# AUDIO2.net
KiCad netlist of a schematic drawn in Altium Designer
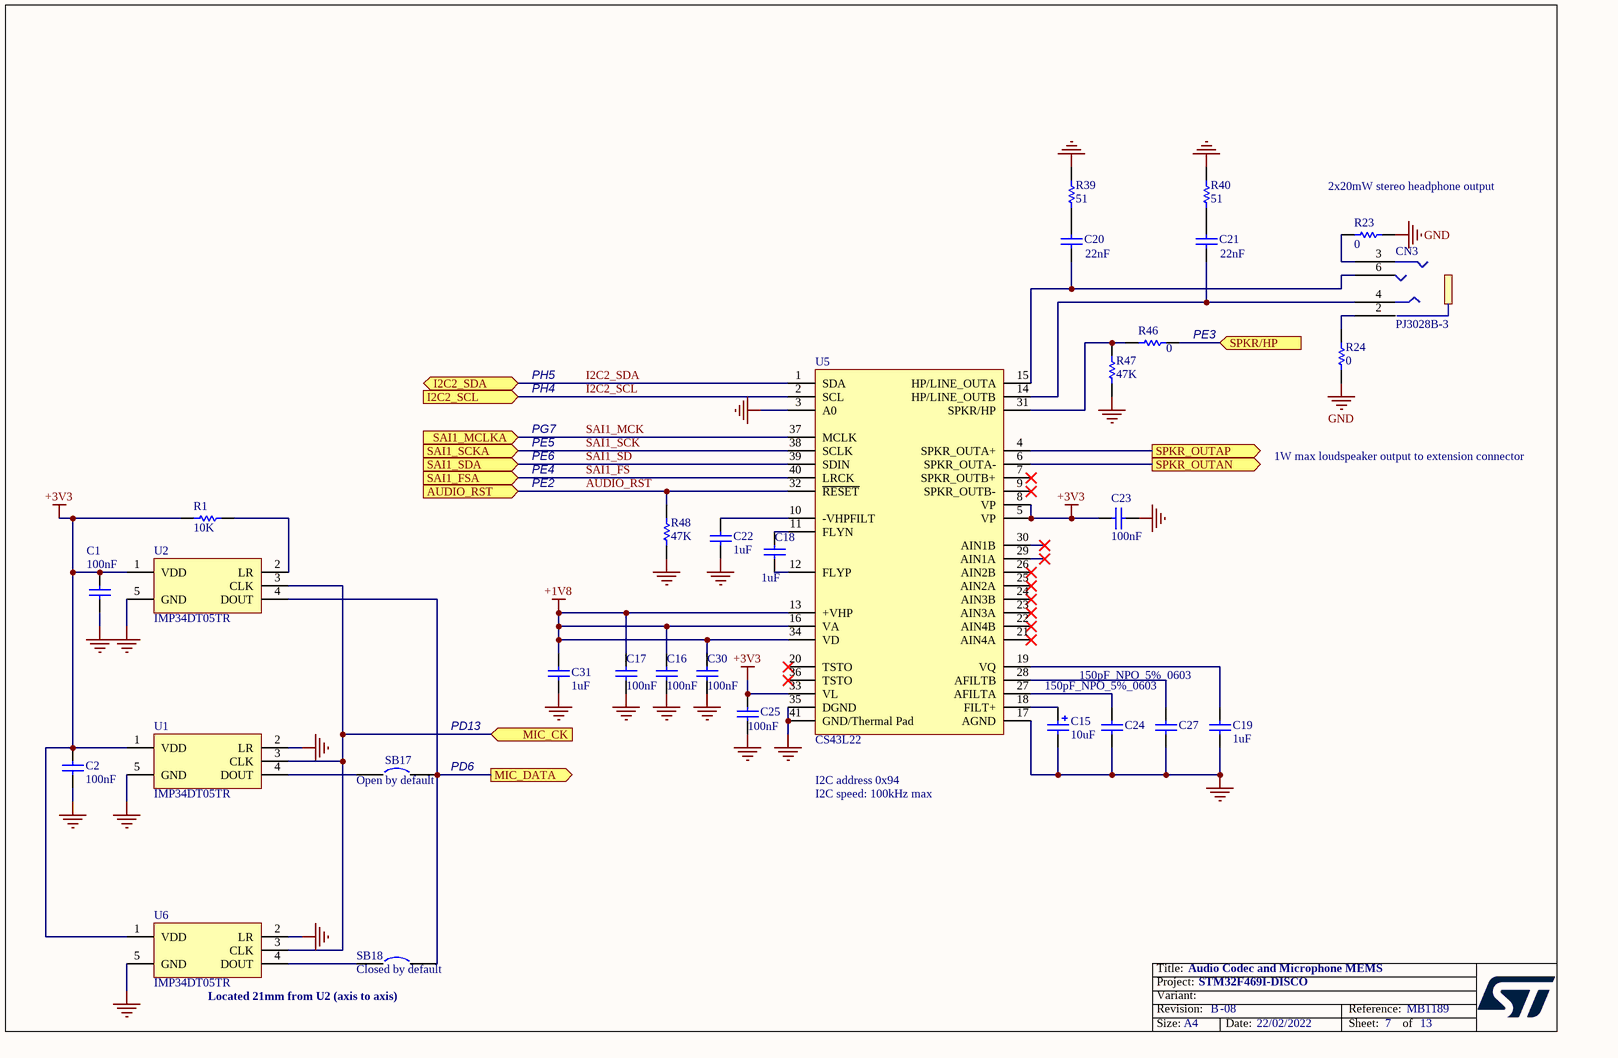
[diagram p0: AUDIO2.SchDoc]

(export (version "E")
  (design (tool "Eeschema 10.0.6"))
  (components
    (comp (ref "C1")
      (value "100nF")
      (footprint "0402C")
      (description "Capacitor")
      (fields (field (name "PUBLISHER") "Altium Limited"))
      (libsource (lib "Miscellaneous Devices") (part "Cap"))
    )
    (comp (ref "C2")
      (value "100nF")
      (footprint "0402C")
      (description "Capacitor")
      (fields (field (name "PUBLISHER") "Altium Limited"))
      (libsource (lib "Miscellaneous Devices") (part "Cap"))
    )
    (comp (ref "C15")
      (value "10uF")
      (footprint "TAN-A")
      (description "Polarized Capacitor (Radial)")
      (fields (field (name "PUBLISHER") "Altium Limited"))
      (libsource (lib "Miscellaneous Devices") (part "Cap Pol1"))
    )
    (comp (ref "C16")
      (value "100nF")
      (footprint "0402C")
      (description "Capacitor")
      (fields (field (name "PUBLISHER") "Altium Limited"))
      (libsource (lib "Miscellaneous Devices") (part "CAP"))
    )
    (comp (ref "C17")
      (value "100nF")
      (footprint "0402C")
      (description "Capacitor")
      (fields (field (name "PUBLISHER") "Altium Limited"))
      (libsource (lib "Miscellaneous Devices") (part "CAP"))
    )
    (comp (ref "C18")
      (value "1uF")
      (footprint "0603C")
      (description "Capacitor")
      (fields (field (name "PUBLISHER") "Altium Limited"))
      (libsource (lib "Miscellaneous Devices") (part "CAP"))
    )
    (comp (ref "C19")
      (value "1uF")
      (footprint "0603C")
      (description "Capacitor")
      (fields (field (name "PUBLISHER") "Altium Limited"))
      (libsource (lib "Miscellaneous Devices") (part "CAP"))
    )
    (comp (ref "C20")
      (value "22nF")
      (footprint "0603C")
      (description "Capacitor,22nF,50V,X7R,10%,0603,YAGEO")
      (libsource (lib "MCD_TOOLS") (part "Cap_22nF_X7R_10%_0603"))
    )
    (comp (ref "C21")
      (value "22nF")
      (footprint "0603C")
      (description "Capacitor,22nF,50V,X7R,10%,0603,YAGEO")
      (libsource (lib "MCD_TOOLS") (part "Cap_22nF_X7R_10%_0603"))
    )
    (comp (ref "C22")
      (value "1uF")
      (footprint "0603C")
      (description "Capacitor")
      (fields (field (name "PUBLISHER") "Altium Limited"))
      (libsource (lib "Miscellaneous Devices") (part "CAP"))
    )
    (comp (ref "C23")
      (value "100nF")
      (footprint "0402C")
      (description "Capacitor")
      (fields (field (name "PUBLISHER") "Altium Limited"))
      (libsource (lib "Miscellaneous Devices") (part "CAP"))
    )
    (comp (ref "C24")
      (value "150pF_NPO_5%_0603")
      (footprint "0603C")
      (description "Capacitor,150pF,50V,NPO,5%,0603,YAGEO")
      (libsource (lib "MCD_TOOLS") (part "Cap_150pF_NPO_5%_0603"))
    )
    (comp (ref "C25")
      (value "100nF")
      (footprint "0402C")
      (description "Capacitor")
      (fields (field (name "PUBLISHER") "Altium Limited"))
      (libsource (lib "Miscellaneous Devices") (part "CAP"))
    )
    (comp (ref "C27")
      (value "150pF_NPO_5%_0603")
      (footprint "0603C")
      (description "Capacitor,150pF,50V,NPO,5%,0603,YAGEO")
      (libsource (lib "MCD_TOOLS") (part "Cap_150pF_NPO_5%_0603"))
    )
    (comp (ref "C30")
      (value "100nF")
      (footprint "0402C")
      (description "Capacitor")
      (fields (field (name "PUBLISHER") "Altium Limited"))
      (libsource (lib "Miscellaneous Devices") (part "CAP"))
    )
    (comp (ref "C31")
      (value "1uF")
      (footprint "0603C")
      (description "Capacitor")
      (fields (field (name "PUBLISHER") "Altium Limited"))
      (libsource (lib "Miscellaneous Devices") (part "CAP"))
    )
    (comp (ref "CN3") (value "PJ3028B-3") (footprint "PJ3028B") (libsource (lib "MB786") (part "PJ3028B-3")))
    (comp (ref "R1")
      (value "10K")
      (footprint "0603R")
      (description "Resistor")
      (libsource (lib "MCD_TOOLS") (part "Res_0_5%_0402"))
    )
    (comp (ref "R23")
      (value "0")
      (footprint "0603R")
      (description "Resistor")
      (fields (field (name "PUBLISHER") "Altium Limited"))
      (libsource (lib "") (part "Res1_1"))
    )
    (comp (ref "R24")
      (value "0")
      (footprint "0603R")
      (description "Resistor")
      (fields (field (name "PUBLISHER") "Altium Limited"))
      (libsource (lib "") (part "Res1_1"))
    )
    (comp (ref "R39")
      (value "51")
      (footprint "0402R")
      (description "Resistor")
      (libsource (lib "MCD_TOOLS") (part "Res_51_1%_0402"))
    )
    (comp (ref "R40")
      (value "51")
      (footprint "0402R")
      (description "Resistor")
      (libsource (lib "MCD_TOOLS") (part "Res_51_1%_0402"))
    )
    (comp (ref "R46")
      (value "0")
      (footprint "0603R")
      (description "Resistor")
      (fields (field (name "PUBLISHER") "Altium Limited"))
      (libsource (lib "Miscellaneous Devices") (part "Res1"))
    )
    (comp (ref "R47")
      (value "47K")
      (footprint "0603R")
      (description "Resistor")
      (fields (field (name "PUBLISHER") "Altium Limited"))
      (libsource (lib "Miscellaneous Devices") (part "Res1"))
    )
    (comp (ref "R48")
      (value "47K")
      (footprint "0603R")
      (description "Resistor")
      (fields (field (name "PUBLISHER") "Altium Limited"))
      (libsource (lib "Miscellaneous Devices") (part "Res1"))
    )
    (comp (ref "SB17")
      (value "Open by default")
      (footprint "SB_0603")
      (description "Circuit Breaker")
      (fields (field (name "PUBLISHER") "Altium Limited"))
      (libsource (lib "Miscellaneous Devices") (part "Circuit Breaker"))
    )
    (comp (ref "SB18")
      (value "Closed by default")
      (footprint "SB_0603")
      (description "Circuit Breaker")
      (fields (field (name "PUBLISHER") "Altium Limited"))
      (libsource (lib "Miscellaneous Devices") (part "Circuit Breaker"))
    )
    (comp (ref "U1")
      (value "IMP34DT05TR")
      (footprint "MP34DT01TR")
      (description "MEMS audio sensor")
      (libsource (lib "Almos") (part "MP34DT01TR"))
    )
    (comp (ref "U2")
      (value "IMP34DT05TR")
      (footprint "MP34DT01TR")
      (description "MEMS audio sensor")
      (libsource (lib "Almos") (part "MP34DT01TR"))
    )
    (comp (ref "U5")
      (value "CS43L22")
      (footprint "QFN40_0R5_6X6")
      (description "Low Power, Stereo DAC w/Headphone & Speaker Amps")
      (libsource (lib "MCD_TOOLS") (part "CS43L22"))
    )
    (comp (ref "U6")
      (value "IMP34DT05TR")
      (footprint "MP34DT01TR")
      (description "MEMS audio sensor")
      (libsource (lib "Almos") (part "MP34DT01TR"))
    )
  )
  (nets
    (net (code "1") (name "+1V8") (class "Default")
      (node (ref "C16") (pin "1") (pinfunction "1_1") (pintype "passive"))
      (node (ref "C17") (pin "1") (pinfunction "1_1") (pintype "passive"))
      (node (ref "C30") (pin "1") (pinfunction "1_1") (pintype "passive"))
      (node (ref "C31") (pin "1") (pinfunction "1_1") (pintype "passive"))
      (node (ref "U5") (pin "13") (pinfunction "+VHP_13") (pintype "passive"))
      (node (ref "U5") (pin "16") (pinfunction "VA_16") (pintype "passive"))
      (node (ref "U5") (pin "34") (pinfunction "VD_34") (pintype "passive"))
    )
    (net (code "2") (name "+3V3") (class "Default")
      (node (ref "C1") (pin "2") (pinfunction "2_2") (pintype "passive"))
      (node (ref "C2") (pin "2") (pinfunction "2_2") (pintype "passive"))
      (node (ref "C23") (pin "2") (pinfunction "2_2") (pintype "passive"))
      (node (ref "C25") (pin "1") (pinfunction "1_1") (pintype "passive"))
      (node (ref "R1") (pin "2") (pinfunction "2_2") (pintype "passive"))
      (node (ref "U1") (pin "1") (pinfunction "VDD_1") (pintype "passive"))
      (node (ref "U2") (pin "1") (pinfunction "VDD_1") (pintype "passive"))
      (node (ref "U5") (pin "33") (pinfunction "VL_33") (pintype "passive"))
      (node (ref "U5") (pin "5") (pinfunction "VP_5") (pintype "passive"))
      (node (ref "U5") (pin "8") (pinfunction "VP_8") (pintype "passive"))
      (node (ref "U6") (pin "1") (pinfunction "VDD_1") (pintype "passive"))
    )
    (net (code "3") (name "/AUDIO_RST") (class "Default")
      (node (ref "R48") (pin "2") (pinfunction "2_2") (pintype "passive"))
      (node (ref "U5") (pin "32") (pinfunction "~{RESET}_32") (pintype "passive"))
    )
    (net (code "4") (name "/I2C2_SCL") (class "Default")
      (node (ref "U5") (pin "2") (pinfunction "SCL_2") (pintype "passive"))
    )
    (net (code "5") (name "/I2C2_SDA") (class "Default")
      (node (ref "U5") (pin "1") (pinfunction "SDA_1") (pintype "passive"))
    )
    (net (code "6") (name "/MIC_CK") (class "Default")
      (node (ref "U1") (pin "3") (pinfunction "CLK_3") (pintype "passive"))
      (node (ref "U2") (pin "3") (pinfunction "CLK_3") (pintype "passive"))
      (node (ref "U6") (pin "3") (pinfunction "CLK_3") (pintype "passive"))
    )
    (net (code "7") (name "/MIC_DATA") (class "Default")
      (node (ref "SB17") (pin "2") (pinfunction "2_2") (pintype "passive"))
      (node (ref "SB18") (pin "2") (pinfunction "2_2") (pintype "passive"))
      (node (ref "U2") (pin "4") (pinfunction "DOUT_4") (pintype "passive"))
    )
    (net (code "8") (name "/SAI1_FS") (class "Default")
      (node (ref "U5") (pin "40") (pinfunction "LRCK_40") (pintype "passive"))
    )
    (net (code "9") (name "/SAI1_MCK") (class "Default")
      (node (ref "U5") (pin "37") (pinfunction "MCLK_37") (pintype "passive"))
    )
    (net (code "10") (name "/SAI1_SCK") (class "Default")
      (node (ref "U5") (pin "38") (pinfunction "SCLK_38") (pintype "passive"))
    )
    (net (code "11") (name "/SAI1_SD") (class "Default")
      (node (ref "U5") (pin "39") (pinfunction "SDIN_39") (pintype "passive"))
    )
    (net (code "12") (name "/SPKR_OUTAN") (class "Default")
      (node (ref "U5") (pin "6") (pinfunction "SPKR_OUTA-_6") (pintype "passive"))
    )
    (net (code "13") (name "/SPKR_OUTAP") (class "Default")
      (node (ref "U5") (pin "4") (pinfunction "SPKR_OUTA+_4") (pintype "passive"))
    )
    (net (code "14") (name "/SPKR{slash}HP") (class "Default")
      (node (ref "R46") (pin "2") (pinfunction "2_2") (pintype "passive"))
    )
    (net (code "15") (name "GND") (class "Default")
      (node (ref "C1") (pin "1") (pinfunction "1_1") (pintype "passive"))
      (node (ref "C15") (pin "2") (pinfunction "2_2") (pintype "passive"))
      (node (ref "C16") (pin "2") (pinfunction "2_2") (pintype "passive"))
      (node (ref "C17") (pin "2") (pinfunction "2_2") (pintype "passive"))
      (node (ref "C19") (pin "1") (pinfunction "1_1") (pintype "passive"))
      (node (ref "C2") (pin "1") (pinfunction "1_1") (pintype "passive"))
      (node (ref "C22") (pin "1") (pinfunction "1_1") (pintype "passive"))
      (node (ref "C23") (pin "1") (pinfunction "1_1") (pintype "passive"))
      (node (ref "C24") (pin "1") (pinfunction "1_1") (pintype "passive"))
      (node (ref "C25") (pin "2") (pinfunction "2_2") (pintype "passive"))
      (node (ref "C27") (pin "1") (pinfunction "1_1") (pintype "passive"))
      (node (ref "C30") (pin "2") (pinfunction "2_2") (pintype "passive"))
      (node (ref "C31") (pin "2") (pinfunction "2_2") (pintype "passive"))
      (node (ref "R23") (pin "2") (pinfunction "2_2") (pintype "passive"))
      (node (ref "R24") (pin "2") (pinfunction "2_2") (pintype "passive"))
      (node (ref "R39") (pin "2") (pinfunction "2_2") (pintype "passive"))
      (node (ref "R40") (pin "2") (pinfunction "2_2") (pintype "passive"))
      (node (ref "R47") (pin "2") (pinfunction "2_2") (pintype "passive"))
      (node (ref "R48") (pin "1") (pinfunction "1_1") (pintype "passive"))
      (node (ref "U1") (pin "2") (pinfunction "LR_2") (pintype "passive"))
      (node (ref "U1") (pin "5") (pinfunction "GND_5") (pintype "passive"))
      (node (ref "U2") (pin "5") (pinfunction "GND_5") (pintype "passive"))
      (node (ref "U5") (pin "17") (pinfunction "AGND_17") (pintype "passive"))
      (node (ref "U5") (pin "3") (pinfunction "A0_3") (pintype "passive"))
      (node (ref "U5") (pin "35") (pinfunction "DGND_35") (pintype "passive"))
      (node (ref "U5") (pin "41") (pinfunction "GND/Thermal_Pad_41") (pintype "passive"))
      (node (ref "U6") (pin "2") (pinfunction "LR_2") (pintype "passive"))
      (node (ref "U6") (pin "5") (pinfunction "GND_5") (pintype "passive"))
    )
    (net (code "16") (name "Net-(C20-Pad2)") (class "Default")
      (node (ref "C20") (pin "2") (pinfunction "2_2") (pintype "passive"))
      (node (ref "R39") (pin "1") (pinfunction "1_1") (pintype "passive"))
    )
    (net (code "17") (name "Net-(C21-Pad2)") (class "Default")
      (node (ref "C21") (pin "2") (pinfunction "2_2") (pintype "passive"))
      (node (ref "R40") (pin "1") (pinfunction "1_1") (pintype "passive"))
    )
    (net (code "18") (name "Net-(CN3-Pad2)") (class "Default")
      (node (ref "CN3") (pin "2") (pintype "passive"))
      (node (ref "R24") (pin "1") (pinfunction "1_1") (pintype "passive"))
    )
    (net (code "19") (name "Net-(CN3-Pad3)") (class "Default")
      (node (ref "CN3") (pin "3") (pintype "passive"))
      (node (ref "R23") (pin "1") (pinfunction "1_1") (pintype "passive"))
    )
    (net (code "20") (name "Net-(U1-DOUT)") (class "Default")
      (node (ref "SB17") (pin "1") (pinfunction "1_1") (pintype "passive"))
      (node (ref "U1") (pin "4") (pinfunction "DOUT_4") (pintype "passive"))
    )
    (net (code "21") (name "Net-(U2-LR)") (class "Default")
      (node (ref "R1") (pin "1") (pinfunction "1_1") (pintype "passive"))
      (node (ref "U2") (pin "2") (pinfunction "LR_2") (pintype "passive"))
    )
    (net (code "22") (name "Net-(U5--VHPFILT)") (class "Default")
      (node (ref "C22") (pin "2") (pinfunction "2_2") (pintype "passive"))
      (node (ref "U5") (pin "10") (pinfunction "-VHPFILT_10") (pintype "passive"))
    )
    (net (code "23") (name "Net-(U5-AFILTA)") (class "Default")
      (node (ref "C24") (pin "2") (pinfunction "2_2") (pintype "passive"))
      (node (ref "U5") (pin "27") (pinfunction "AFILTA_27") (pintype "passive"))
    )
    (net (code "24") (name "Net-(U5-AFILTB)") (class "Default")
      (node (ref "C27") (pin "2") (pinfunction "2_2") (pintype "passive"))
      (node (ref "U5") (pin "28") (pinfunction "AFILTB_28") (pintype "passive"))
    )
    (net (code "25") (name "Net-(U5-FILT+)") (class "Default")
      (node (ref "C15") (pin "1") (pinfunction "1_1") (pintype "passive"))
      (node (ref "U5") (pin "18") (pinfunction "FILT+_18") (pintype "passive"))
    )
    (net (code "26") (name "Net-(U5-FLYN)") (class "Default")
      (node (ref "C18") (pin "1") (pinfunction "1_1") (pintype "passive"))
      (node (ref "U5") (pin "11") (pinfunction "FLYN_11") (pintype "passive"))
    )
    (net (code "27") (name "Net-(U5-FLYP)") (class "Default")
      (node (ref "C18") (pin "2") (pinfunction "2_2") (pintype "passive"))
      (node (ref "U5") (pin "12") (pinfunction "FLYP_12") (pintype "passive"))
    )
    (net (code "28") (name "Net-(U5-HP{slash}LINE_OUTA)") (class "Default")
      (node (ref "C20") (pin "1") (pinfunction "1_1") (pintype "passive"))
      (node (ref "CN3") (pin "6") (pintype "passive"))
      (node (ref "U5") (pin "15") (pinfunction "HP/LINE_OUTA_15") (pintype "passive"))
    )
    (net (code "29") (name "Net-(U5-HP{slash}LINE_OUTB)") (class "Default")
      (node (ref "C21") (pin "1") (pinfunction "1_1") (pintype "passive"))
      (node (ref "CN3") (pin "4") (pintype "passive"))
      (node (ref "U5") (pin "14") (pinfunction "HP/LINE_OUTB_14") (pintype "passive"))
    )
    (net (code "30") (name "Net-(U5-SPKR{slash}HP)") (class "Default")
      (node (ref "R46") (pin "1") (pinfunction "1_1") (pintype "passive"))
      (node (ref "R47") (pin "1") (pinfunction "1_1") (pintype "passive"))
      (node (ref "U5") (pin "31") (pinfunction "SPKR/HP_31") (pintype "passive"))
    )
    (net (code "31") (name "Net-(U5-VQ)") (class "Default")
      (node (ref "C19") (pin "2") (pinfunction "2_2") (pintype "passive"))
      (node (ref "U5") (pin "19") (pinfunction "VQ_19") (pintype "passive"))
    )
    (net (code "32") (name "Net-(U6-DOUT)") (class "Default")
      (node (ref "SB18") (pin "1") (pinfunction "1_1") (pintype "passive"))
      (node (ref "U6") (pin "4") (pinfunction "DOUT_4") (pintype "passive"))
    )
    (net (code "33") (name "unconnected-(U5-AIN1A-Pad29)") (class "Default")
      (node (ref "U5") (pin "29") (pinfunction "AIN1A_29") (pintype "passive+no_connect"))
    )
    (net (code "34") (name "unconnected-(U5-AIN1B-Pad30)") (class "Default")
      (node (ref "U5") (pin "30") (pinfunction "AIN1B_30") (pintype "passive+no_connect"))
    )
    (net (code "35") (name "unconnected-(U5-AIN2A-Pad25)") (class "Default")
      (node (ref "U5") (pin "25") (pinfunction "AIN2A_25") (pintype "passive+no_connect"))
    )
    (net (code "36") (name "unconnected-(U5-AIN2B-Pad26)") (class "Default")
      (node (ref "U5") (pin "26") (pinfunction "AIN2B_26") (pintype "passive+no_connect"))
    )
    (net (code "37") (name "unconnected-(U5-AIN3A-Pad23)") (class "Default")
      (node (ref "U5") (pin "23") (pinfunction "AIN3A_23") (pintype "passive+no_connect"))
    )
    (net (code "38") (name "unconnected-(U5-AIN3B-Pad24)") (class "Default")
      (node (ref "U5") (pin "24") (pinfunction "AIN3B_24") (pintype "passive+no_connect"))
    )
    (net (code "39") (name "unconnected-(U5-AIN4A-Pad21)") (class "Default")
      (node (ref "U5") (pin "21") (pinfunction "AIN4A_21") (pintype "passive+no_connect"))
    )
    (net (code "40") (name "unconnected-(U5-AIN4B-Pad22)") (class "Default")
      (node (ref "U5") (pin "22") (pinfunction "AIN4B_22") (pintype "passive+no_connect"))
    )
    (net (code "41") (name "unconnected-(U5-SPKR_OUTB+-Pad7)") (class "Default")
      (node (ref "U5") (pin "7") (pinfunction "SPKR_OUTB+_7") (pintype "passive+no_connect"))
    )
    (net (code "42") (name "unconnected-(U5-SPKR_OUTB--Pad9)") (class "Default")
      (node (ref "U5") (pin "9") (pinfunction "SPKR_OUTB-_9") (pintype "passive+no_connect"))
    )
    (net (code "43") (name "unconnected-(U5-TSTO-Pad20)") (class "Default")
      (node (ref "U5") (pin "20") (pinfunction "TSTO_20") (pintype "passive+no_connect"))
    )
    (net (code "44") (name "unconnected-(U5-TSTO-Pad36)") (class "Default")
      (node (ref "U5") (pin "36") (pinfunction "TSTO_36") (pintype "passive+no_connect"))
    )
  )
)
